# flute.net
KiCad netlist of a schematic drawn in EAGLE
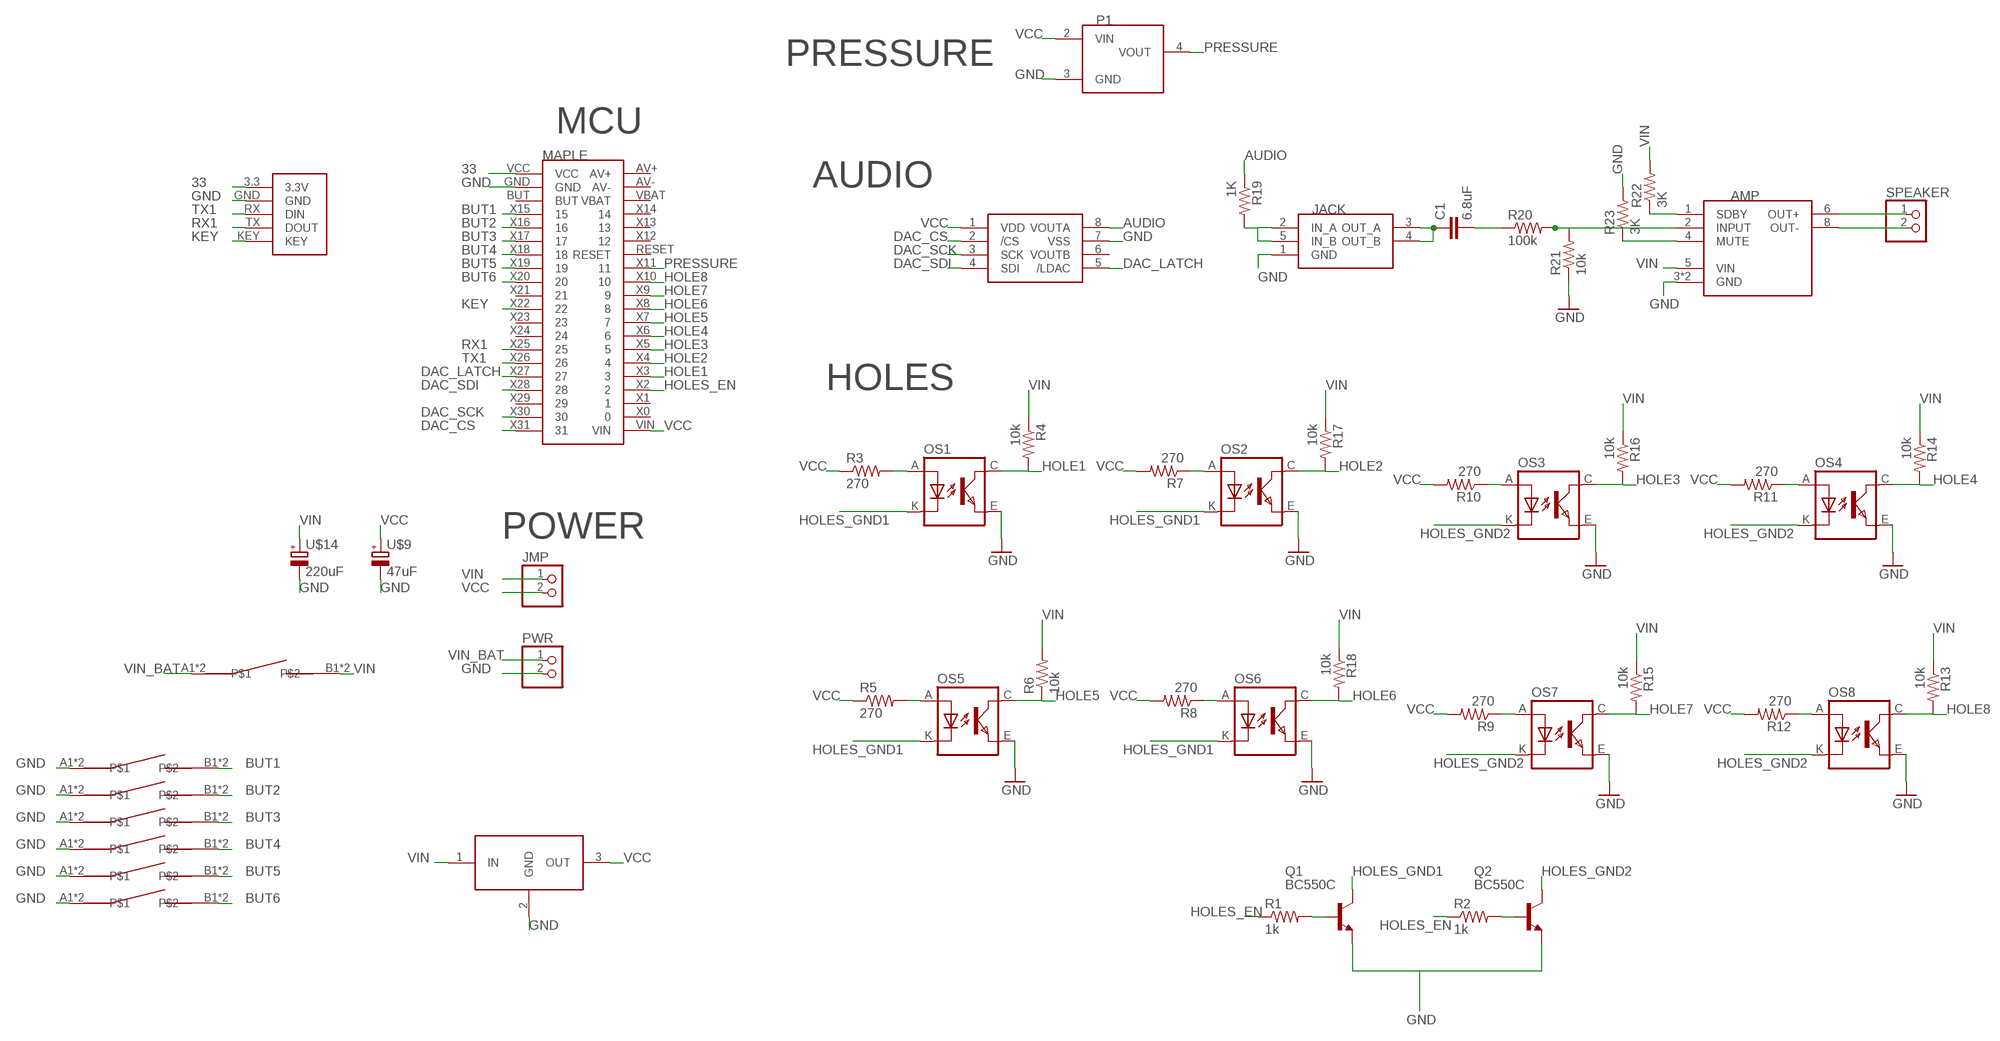
[diagram p0: schematic, sheet 1]

(export (version "E")
  (design (tool "Eeschema 10.0.6"))
  (components
    (comp (ref "AMP")
      (value "AN7511DIP8")
      (footprint "eagle-import:DIL08")
      (libsource (lib "eagle-import") (part "AN7511DIP8"))
    )
    (comp (ref "C1")
      (value "6.8uF")
      (footprint "eagle-import:0805")
      (libsource (lib "eagle-import") (part "CAP0805"))
    )
    (comp (ref "JACK")
      (value "JACK")
      (footprint "eagle-import:3F07")
      (libsource (lib "eagle-import") (part "JACK"))
    )
    (comp (ref "JMP")
      (value "CONNEC_1X02BASIC")
      (footprint "eagle-import:CONNEC_1X02")
      (libsource (lib "eagle-import") (part "CONNEC_1X02BASIC"))
    )
    (comp (ref "MAPLE")
      (value "MAPLE_MINI")
      (footprint "eagle-import:CONNEC_2X20")
      (libsource (lib "eagle-import") (part "MAPLE_MINI"))
    )
    (comp (ref "OS1")
      (value "TCRT5000")
      (footprint "eagle-import:TCRT5000")
      (libsource (lib "eagle-import") (part "TCRT5000"))
    )
    (comp (ref "OS2")
      (value "TCRT5000")
      (footprint "eagle-import:TCRT5000")
      (libsource (lib "eagle-import") (part "TCRT5000"))
    )
    (comp (ref "OS3")
      (value "TCRT5000")
      (footprint "eagle-import:TCRT5000")
      (libsource (lib "eagle-import") (part "TCRT5000"))
    )
    (comp (ref "OS4")
      (value "TCRT5000")
      (footprint "eagle-import:TCRT5000")
      (libsource (lib "eagle-import") (part "TCRT5000"))
    )
    (comp (ref "OS5")
      (value "TCRT5000")
      (footprint "eagle-import:TCRT5000")
      (libsource (lib "eagle-import") (part "TCRT5000"))
    )
    (comp (ref "OS6")
      (value "TCRT5000")
      (footprint "eagle-import:TCRT5000")
      (libsource (lib "eagle-import") (part "TCRT5000"))
    )
    (comp (ref "OS7")
      (value "TCRT5000")
      (footprint "eagle-import:TCRT5000")
      (libsource (lib "eagle-import") (part "TCRT5000"))
    )
    (comp (ref "OS8")
      (value "TCRT5000")
      (footprint "eagle-import:TCRT5000")
      (libsource (lib "eagle-import") (part "TCRT5000"))
    )
    (comp (ref "P1")
      (value "PRESSURE_SENSOR")
      (footprint "eagle-import:MPXV5050GP")
      (libsource (lib "eagle-import") (part "PRESSURE_SENSOR"))
    )
    (comp (ref "PWR")
      (value "CONNEC_1X02BASIC")
      (footprint "eagle-import:CONNEC_1X02")
      (libsource (lib "eagle-import") (part "CONNEC_1X02BASIC"))
    )
    (comp (ref "Q1")
      (value "BC550C")
      (footprint "eagle-import:TO92-EBC")
      (libsource (lib "eagle-import") (part "BC550C"))
    )
    (comp (ref "Q2")
      (value "BC550C")
      (footprint "eagle-import:TO92-EBC")
      (libsource (lib "eagle-import") (part "BC550C"))
    )
    (comp (ref "R1")
      (value "1k")
      (footprint "eagle-import:0805")
      (libsource (lib "eagle-import") (part "RESISTOR0805-RES"))
    )
    (comp (ref "R2")
      (value "1k")
      (footprint "eagle-import:0805")
      (libsource (lib "eagle-import") (part "RESISTOR0805-RES"))
    )
    (comp (ref "R3")
      (value "270")
      (footprint "eagle-import:0805")
      (libsource (lib "eagle-import") (part "RESISTOR0805-RES"))
    )
    (comp (ref "R4")
      (value "10k")
      (footprint "eagle-import:0805")
      (libsource (lib "eagle-import") (part "RESISTOR0805-RES"))
    )
    (comp (ref "R5")
      (value "270")
      (footprint "eagle-import:0805")
      (libsource (lib "eagle-import") (part "RESISTOR0805-RES"))
    )
    (comp (ref "R6")
      (value "10k")
      (footprint "eagle-import:0805")
      (libsource (lib "eagle-import") (part "RESISTOR0805-RES"))
    )
    (comp (ref "R7")
      (value "270")
      (footprint "eagle-import:0805")
      (libsource (lib "eagle-import") (part "RESISTOR0805-RES"))
    )
    (comp (ref "R8")
      (value "270")
      (footprint "eagle-import:0805")
      (libsource (lib "eagle-import") (part "RESISTOR0805-RES"))
    )
    (comp (ref "R9")
      (value "270")
      (footprint "eagle-import:0805")
      (libsource (lib "eagle-import") (part "RESISTOR0805-RES"))
    )
    (comp (ref "R10")
      (value "270")
      (footprint "eagle-import:0805")
      (libsource (lib "eagle-import") (part "RESISTOR0805-RES"))
    )
    (comp (ref "R11")
      (value "270")
      (footprint "eagle-import:0805")
      (libsource (lib "eagle-import") (part "RESISTOR0805-RES"))
    )
    (comp (ref "R12")
      (value "270")
      (footprint "eagle-import:0805")
      (libsource (lib "eagle-import") (part "RESISTOR0805-RES"))
    )
    (comp (ref "R13")
      (value "10k")
      (footprint "eagle-import:0805")
      (libsource (lib "eagle-import") (part "RESISTOR0805-RES"))
    )
    (comp (ref "R14")
      (value "10k")
      (footprint "eagle-import:0805")
      (libsource (lib "eagle-import") (part "RESISTOR0805-RES"))
    )
    (comp (ref "R15")
      (value "10k")
      (footprint "eagle-import:0805")
      (libsource (lib "eagle-import") (part "RESISTOR0805-RES"))
    )
    (comp (ref "R16")
      (value "10k")
      (footprint "eagle-import:0805")
      (libsource (lib "eagle-import") (part "RESISTOR0805-RES"))
    )
    (comp (ref "R17")
      (value "10k")
      (footprint "eagle-import:0805")
      (libsource (lib "eagle-import") (part "RESISTOR0805-RES"))
    )
    (comp (ref "R18")
      (value "10k")
      (footprint "eagle-import:0805")
      (libsource (lib "eagle-import") (part "RESISTOR0805-RES"))
    )
    (comp (ref "R19")
      (value "1K")
      (footprint "eagle-import:0805")
      (libsource (lib "eagle-import") (part "RESISTOR0805-RES"))
    )
    (comp (ref "R20")
      (value "100k")
      (footprint "eagle-import:0805")
      (libsource (lib "eagle-import") (part "RESISTOR0805-RES"))
    )
    (comp (ref "R21")
      (value "10k")
      (footprint "eagle-import:0805")
      (libsource (lib "eagle-import") (part "RESISTOR0805-RES"))
    )
    (comp (ref "R22")
      (value "3K")
      (footprint "eagle-import:0805")
      (libsource (lib "eagle-import") (part "RESISTOR0805-RES"))
    )
    (comp (ref "R23")
      (value "3K")
      (footprint "eagle-import:0805")
      (libsource (lib "eagle-import") (part "RESISTOR0805-RES"))
    )
    (comp (ref "SPEAKER")
      (value "CONNEC_1X02BASIC")
      (footprint "eagle-import:CONNEC_1X02")
      (libsource (lib "eagle-import") (part "CONNEC_1X02BASIC"))
    )
    (comp (ref "U$9")
      (value "47uF")
      (footprint "eagle-import:PANASONIC_D")
      (libsource (lib "eagle-import") (part "CPOL_EUPANASONIC_D"))
    )
    (comp (ref "U$14")
      (value "220uF")
      (footprint "eagle-import:PANASONIC_D8")
      (libsource (lib "eagle-import") (part "CPOL_EUPANASONIC_D8"))
    )
    (comp (ref "U$16")
      (value "SWITCHKCD11")
      (footprint "eagle-import:KCD11")
      (libsource (lib "eagle-import") (part "SWITCHKCD11"))
    )
    (comp (ref "U$17")
      (value "MCP4822")
      (footprint "eagle-import:DIL08")
      (libsource (lib "eagle-import") (part "RHOBAN_MCP4822"))
    )
    (comp (ref "U$18")
      (value "SWITCH6X6X10")
      (footprint "eagle-import:SWITCH_6X6X10")
      (libsource (lib "eagle-import") (part "SWITCH6X6X10"))
    )
    (comp (ref "U$19")
      (value "SWITCH6X6X10")
      (footprint "eagle-import:SWITCH_6X6X10")
      (libsource (lib "eagle-import") (part "SWITCH6X6X10"))
    )
    (comp (ref "U$20")
      (value "SWITCH6X6X10")
      (footprint "eagle-import:SWITCH_6X6X10")
      (libsource (lib "eagle-import") (part "SWITCH6X6X10"))
    )
    (comp (ref "U$21")
      (value "SWITCH6X6X10")
      (footprint "eagle-import:SWITCH_6X6X10")
      (libsource (lib "eagle-import") (part "SWITCH6X6X10"))
    )
    (comp (ref "U$22")
      (value "SWITCH6X6X10")
      (footprint "eagle-import:SWITCH_6X6X10")
      (libsource (lib "eagle-import") (part "SWITCH6X6X10"))
    )
    (comp (ref "U$23")
      (value "SWITCH6X6X10")
      (footprint "eagle-import:SWITCH_6X6X10")
      (libsource (lib "eagle-import") (part "SWITCH6X6X10"))
    )
    (comp (ref "U$24")
      (value "HC05")
      (footprint "eagle-import:HC-05")
      (libsource (lib "eagle-import") (part "HC05"))
    )
    (comp (ref "U$25")
      (value "MCP1703T-5002EDB")
      (footprint "eagle-import:SOT223")
      (libsource (lib "eagle-import") (part "MCP1703T-5002EDB"))
    )
  )
  (nets
    (net (code "1") (name "/33") (class "Default")
      (node (ref "MAPLE") (pin "VCC") (pinfunction "VCC_VCC") (pintype "bidirectional"))
      (node (ref "U$24") (pin "3.3") (pinfunction "3.3V_3.3") (pintype "bidirectional"))
    )
    (net (code "2") (name "/AUDIO") (class "Default")
      (node (ref "R19") (pin "1") (pinfunction "1_1") (pintype "passive"))
      (node (ref "U$17") (pin "8") (pinfunction "VOUTA_8") (pintype "bidirectional"))
    )
    (net (code "3") (name "/BUT1") (class "Default")
      (node (ref "MAPLE") (pin "X15") (pinfunction "15_X15") (pintype "bidirectional"))
      (node (ref "U$18") (pin "B1") (pinfunction "P$2_B1") (pintype "bidirectional"))
      (node (ref "U$18") (pin "B2") (pinfunction "P$2_B2") (pintype "bidirectional"))
    )
    (net (code "4") (name "/BUT2") (class "Default")
      (node (ref "MAPLE") (pin "X16") (pinfunction "16_X16") (pintype "bidirectional"))
      (node (ref "U$19") (pin "B1") (pinfunction "P$2_B1") (pintype "bidirectional"))
      (node (ref "U$19") (pin "B2") (pinfunction "P$2_B2") (pintype "bidirectional"))
    )
    (net (code "5") (name "/BUT3") (class "Default")
      (node (ref "MAPLE") (pin "X17") (pinfunction "17_X17") (pintype "bidirectional"))
      (node (ref "U$20") (pin "B1") (pinfunction "P$2_B1") (pintype "bidirectional"))
      (node (ref "U$20") (pin "B2") (pinfunction "P$2_B2") (pintype "bidirectional"))
    )
    (net (code "6") (name "/BUT4") (class "Default")
      (node (ref "MAPLE") (pin "X18") (pinfunction "18_X18") (pintype "bidirectional"))
      (node (ref "U$21") (pin "B1") (pinfunction "P$2_B1") (pintype "bidirectional"))
      (node (ref "U$21") (pin "B2") (pinfunction "P$2_B2") (pintype "bidirectional"))
    )
    (net (code "7") (name "/BUT5") (class "Default")
      (node (ref "MAPLE") (pin "X19") (pinfunction "19_X19") (pintype "bidirectional"))
      (node (ref "U$22") (pin "B1") (pinfunction "P$2_B1") (pintype "bidirectional"))
      (node (ref "U$22") (pin "B2") (pinfunction "P$2_B2") (pintype "bidirectional"))
    )
    (net (code "8") (name "/BUT6") (class "Default")
      (node (ref "MAPLE") (pin "X20") (pinfunction "20_X20") (pintype "bidirectional"))
      (node (ref "U$23") (pin "B1") (pinfunction "P$2_B1") (pintype "bidirectional"))
      (node (ref "U$23") (pin "B2") (pinfunction "P$2_B2") (pintype "bidirectional"))
    )
    (net (code "9") (name "/DAC_CS") (class "Default")
      (node (ref "MAPLE") (pin "X31") (pinfunction "31_X31") (pintype "bidirectional"))
      (node (ref "U$17") (pin "2") (pinfunction "/CS_2") (pintype "bidirectional"))
    )
    (net (code "10") (name "/DAC_LATCH") (class "Default")
      (node (ref "MAPLE") (pin "X27") (pinfunction "27_X27") (pintype "bidirectional"))
      (node (ref "U$17") (pin "5") (pinfunction "/LDAC_5") (pintype "bidirectional"))
    )
    (net (code "11") (name "/DAC_SCK") (class "Default")
      (node (ref "MAPLE") (pin "X30") (pinfunction "30_X30") (pintype "bidirectional"))
      (node (ref "U$17") (pin "3") (pinfunction "SCK_3") (pintype "bidirectional"))
    )
    (net (code "12") (name "/DAC_SDI") (class "Default")
      (node (ref "MAPLE") (pin "X28") (pinfunction "28_X28") (pintype "bidirectional"))
      (node (ref "U$17") (pin "4") (pinfunction "SDI_4") (pintype "bidirectional"))
    )
    (net (code "13") (name "/HOLE1") (class "Default")
      (node (ref "MAPLE") (pin "X3") (pinfunction "3_X3") (pintype "bidirectional"))
      (node (ref "OS1") (pin "C") (pinfunction "COLLECTOR_C") (pintype "passive"))
      (node (ref "R4") (pin "2") (pinfunction "2_2") (pintype "passive"))
    )
    (net (code "14") (name "/HOLE2") (class "Default")
      (node (ref "MAPLE") (pin "X4") (pinfunction "4_X4") (pintype "bidirectional"))
      (node (ref "OS2") (pin "C") (pinfunction "COLLECTOR_C") (pintype "passive"))
      (node (ref "R17") (pin "2") (pinfunction "2_2") (pintype "passive"))
    )
    (net (code "15") (name "/HOLE3") (class "Default")
      (node (ref "MAPLE") (pin "X5") (pinfunction "5_X5") (pintype "bidirectional"))
      (node (ref "OS3") (pin "C") (pinfunction "COLLECTOR_C") (pintype "passive"))
      (node (ref "R16") (pin "2") (pinfunction "2_2") (pintype "passive"))
    )
    (net (code "16") (name "/HOLE4") (class "Default")
      (node (ref "MAPLE") (pin "X6") (pinfunction "6_X6") (pintype "bidirectional"))
      (node (ref "OS4") (pin "C") (pinfunction "COLLECTOR_C") (pintype "passive"))
      (node (ref "R14") (pin "2") (pinfunction "2_2") (pintype "passive"))
    )
    (net (code "17") (name "/HOLE5") (class "Default")
      (node (ref "MAPLE") (pin "X7") (pinfunction "7_X7") (pintype "bidirectional"))
      (node (ref "OS5") (pin "C") (pinfunction "COLLECTOR_C") (pintype "passive"))
      (node (ref "R6") (pin "1") (pinfunction "1_1") (pintype "passive"))
    )
    (net (code "18") (name "/HOLE6") (class "Default")
      (node (ref "MAPLE") (pin "X8") (pinfunction "8_X8") (pintype "bidirectional"))
      (node (ref "OS6") (pin "C") (pinfunction "COLLECTOR_C") (pintype "passive"))
      (node (ref "R18") (pin "2") (pinfunction "2_2") (pintype "passive"))
    )
    (net (code "19") (name "/HOLE7") (class "Default")
      (node (ref "MAPLE") (pin "X9") (pinfunction "9_X9") (pintype "bidirectional"))
      (node (ref "OS7") (pin "C") (pinfunction "COLLECTOR_C") (pintype "passive"))
      (node (ref "R15") (pin "2") (pinfunction "2_2") (pintype "passive"))
    )
    (net (code "20") (name "/HOLE8") (class "Default")
      (node (ref "MAPLE") (pin "X10") (pinfunction "10_X10") (pintype "bidirectional"))
      (node (ref "OS8") (pin "C") (pinfunction "COLLECTOR_C") (pintype "passive"))
      (node (ref "R13") (pin "2") (pinfunction "2_2") (pintype "passive"))
    )
    (net (code "21") (name "/HOLES_EN") (class "Default")
      (node (ref "MAPLE") (pin "X2") (pinfunction "2_X2") (pintype "bidirectional"))
      (node (ref "R1") (pin "1") (pinfunction "1_1") (pintype "passive"))
      (node (ref "R2") (pin "1") (pinfunction "1_1") (pintype "passive"))
    )
    (net (code "22") (name "/HOLES_GND1") (class "Default")
      (node (ref "OS1") (pin "K") (pinfunction "CATHODE_K") (pintype "passive"))
      (node (ref "OS2") (pin "K") (pinfunction "CATHODE_K") (pintype "passive"))
      (node (ref "OS5") (pin "K") (pinfunction "CATHODE_K") (pintype "passive"))
      (node (ref "OS6") (pin "K") (pinfunction "CATHODE_K") (pintype "passive"))
      (node (ref "Q1") (pin "C") (pinfunction "C_C") (pintype "passive"))
    )
    (net (code "23") (name "/HOLES_GND2") (class "Default")
      (node (ref "OS3") (pin "K") (pinfunction "CATHODE_K") (pintype "passive"))
      (node (ref "OS4") (pin "K") (pinfunction "CATHODE_K") (pintype "passive"))
      (node (ref "OS7") (pin "K") (pinfunction "CATHODE_K") (pintype "passive"))
      (node (ref "OS8") (pin "K") (pinfunction "CATHODE_K") (pintype "passive"))
      (node (ref "Q2") (pin "C") (pinfunction "C_C") (pintype "passive"))
    )
    (net (code "24") (name "/KEY") (class "Default")
      (node (ref "MAPLE") (pin "X22") (pinfunction "22_X22") (pintype "bidirectional"))
      (node (ref "U$24") (pin "KEY") (pinfunction "KEY_KEY") (pintype "bidirectional"))
    )
    (net (code "25") (name "/PRESSURE") (class "Default")
      (node (ref "MAPLE") (pin "X11") (pinfunction "11_X11") (pintype "bidirectional"))
      (node (ref "P1") (pin "4") (pinfunction "VOUT_4") (pintype "bidirectional"))
    )
    (net (code "26") (name "/RX1") (class "Default")
      (node (ref "MAPLE") (pin "X25") (pinfunction "25_X25") (pintype "bidirectional"))
      (node (ref "U$24") (pin "TX") (pinfunction "DOUT_TX") (pintype "bidirectional"))
    )
    (net (code "27") (name "/TX1") (class "Default")
      (node (ref "MAPLE") (pin "X26") (pinfunction "26_X26") (pintype "bidirectional"))
      (node (ref "U$24") (pin "RX") (pinfunction "DIN_RX") (pintype "bidirectional"))
    )
    (net (code "28") (name "/VCC") (class "Default")
      (node (ref "JMP") (pin "2") (pinfunction "2_2") (pintype "passive"))
      (node (ref "MAPLE") (pin "VIN") (pinfunction "VIN_VIN") (pintype "bidirectional"))
      (node (ref "P1") (pin "2") (pinfunction "VIN_2") (pintype "bidirectional"))
      (node (ref "R10") (pin "2") (pinfunction "2_2") (pintype "passive"))
      (node (ref "R11") (pin "2") (pinfunction "2_2") (pintype "passive"))
      (node (ref "R12") (pin "2") (pinfunction "2_2") (pintype "passive"))
      (node (ref "R3") (pin "1") (pinfunction "1_1") (pintype "passive"))
      (node (ref "R5") (pin "1") (pinfunction "1_1") (pintype "passive"))
      (node (ref "R7") (pin "2") (pinfunction "2_2") (pintype "passive"))
      (node (ref "R8") (pin "2") (pinfunction "2_2") (pintype "passive"))
      (node (ref "R9") (pin "2") (pinfunction "2_2") (pintype "passive"))
      (node (ref "U$17") (pin "1") (pinfunction "VDD_1") (pintype "bidirectional"))
      (node (ref "U$25") (pin "3") (pinfunction "OUT_3") (pintype "bidirectional"))
      (node (ref "U$9") (pin "+") (pinfunction "+_+") (pintype "passive"))
    )
    (net (code "29") (name "/VIN") (class "Default")
      (node (ref "AMP") (pin "5") (pinfunction "VIN_5") (pintype "bidirectional"))
      (node (ref "JMP") (pin "1") (pinfunction "1_1") (pintype "passive"))
      (node (ref "R13") (pin "1") (pinfunction "1_1") (pintype "passive"))
      (node (ref "R14") (pin "1") (pinfunction "1_1") (pintype "passive"))
      (node (ref "R15") (pin "1") (pinfunction "1_1") (pintype "passive"))
      (node (ref "R16") (pin "1") (pinfunction "1_1") (pintype "passive"))
      (node (ref "R17") (pin "1") (pinfunction "1_1") (pintype "passive"))
      (node (ref "R18") (pin "1") (pinfunction "1_1") (pintype "passive"))
      (node (ref "R22") (pin "2") (pinfunction "2_2") (pintype "passive"))
      (node (ref "R4") (pin "1") (pinfunction "1_1") (pintype "passive"))
      (node (ref "R6") (pin "2") (pinfunction "2_2") (pintype "passive"))
      (node (ref "U$14") (pin "+") (pinfunction "+_+") (pintype "passive"))
      (node (ref "U$16") (pin "B1") (pinfunction "P$2_B1") (pintype "bidirectional"))
      (node (ref "U$16") (pin "B2") (pinfunction "P$2_B2") (pintype "bidirectional"))
      (node (ref "U$25") (pin "1") (pinfunction "IN_1") (pintype "bidirectional"))
    )
    (net (code "30") (name "/VIN_BAT") (class "Default")
      (node (ref "PWR") (pin "1") (pinfunction "1_1") (pintype "passive"))
      (node (ref "U$16") (pin "A1") (pinfunction "P$1_A1") (pintype "bidirectional"))
      (node (ref "U$16") (pin "A2") (pinfunction "P$1_A2") (pintype "bidirectional"))
    )
    (net (code "31") (name "GND") (class "Default")
      (node (ref "AMP") (pin "3") (pinfunction "GND_3") (pintype "bidirectional"))
      (node (ref "AMP") (pin "7") (pinfunction "GND_7") (pintype "bidirectional"))
      (node (ref "JACK") (pin "1") (pinfunction "GND_1") (pintype "bidirectional"))
      (node (ref "MAPLE") (pin "GND") (pinfunction "GND_GND") (pintype "bidirectional"))
      (node (ref "OS1") (pin "E") (pinfunction "EMITTER_E") (pintype "passive"))
      (node (ref "OS2") (pin "E") (pinfunction "EMITTER_E") (pintype "passive"))
      (node (ref "OS3") (pin "E") (pinfunction "EMITTER_E") (pintype "passive"))
      (node (ref "OS4") (pin "E") (pinfunction "EMITTER_E") (pintype "passive"))
      (node (ref "OS5") (pin "E") (pinfunction "EMITTER_E") (pintype "passive"))
      (node (ref "OS6") (pin "E") (pinfunction "EMITTER_E") (pintype "passive"))
      (node (ref "OS7") (pin "E") (pinfunction "EMITTER_E") (pintype "passive"))
      (node (ref "OS8") (pin "E") (pinfunction "EMITTER_E") (pintype "passive"))
      (node (ref "P1") (pin "3") (pinfunction "GND_3") (pintype "bidirectional"))
      (node (ref "PWR") (pin "2") (pinfunction "2_2") (pintype "passive"))
      (node (ref "Q1") (pin "E") (pinfunction "E_E") (pintype "passive"))
      (node (ref "Q2") (pin "E") (pinfunction "E_E") (pintype "passive"))
      (node (ref "R21") (pin "1") (pinfunction "1_1") (pintype "passive"))
      (node (ref "R23") (pin "2") (pinfunction "2_2") (pintype "passive"))
      (node (ref "U$14") (pin "-") (pinfunction "-_-") (pintype "passive"))
      (node (ref "U$17") (pin "7") (pinfunction "VSS_7") (pintype "bidirectional"))
      (node (ref "U$18") (pin "A1") (pinfunction "P$1_A1") (pintype "bidirectional"))
      (node (ref "U$18") (pin "A2") (pinfunction "P$1_A2") (pintype "bidirectional"))
      (node (ref "U$19") (pin "A1") (pinfunction "P$1_A1") (pintype "bidirectional"))
      (node (ref "U$19") (pin "A2") (pinfunction "P$1_A2") (pintype "bidirectional"))
      (node (ref "U$20") (pin "A1") (pinfunction "P$1_A1") (pintype "bidirectional"))
      (node (ref "U$20") (pin "A2") (pinfunction "P$1_A2") (pintype "bidirectional"))
      (node (ref "U$21") (pin "A1") (pinfunction "P$1_A1") (pintype "bidirectional"))
      (node (ref "U$21") (pin "A2") (pinfunction "P$1_A2") (pintype "bidirectional"))
      (node (ref "U$22") (pin "A1") (pinfunction "P$1_A1") (pintype "bidirectional"))
      (node (ref "U$22") (pin "A2") (pinfunction "P$1_A2") (pintype "bidirectional"))
      (node (ref "U$23") (pin "A1") (pinfunction "P$1_A1") (pintype "bidirectional"))
      (node (ref "U$23") (pin "A2") (pinfunction "P$1_A2") (pintype "bidirectional"))
      (node (ref "U$24") (pin "GND") (pinfunction "GND_GND") (pintype "bidirectional"))
      (node (ref "U$25") (pin "2") (pinfunction "GND_2") (pintype "bidirectional"))
      (node (ref "U$9") (pin "-") (pinfunction "-_-") (pintype "passive"))
    )
    (net (code "32") (name "Net-(AMP-INPUT)") (class "Default")
      (node (ref "AMP") (pin "2") (pinfunction "INPUT_2") (pintype "bidirectional"))
      (node (ref "R20") (pin "2") (pinfunction "2_2") (pintype "passive"))
      (node (ref "R21") (pin "2") (pinfunction "2_2") (pintype "passive"))
    )
    (net (code "33") (name "Net-(AMP-MUTE)") (class "Default")
      (node (ref "AMP") (pin "4") (pinfunction "MUTE_4") (pintype "bidirectional"))
      (node (ref "R23") (pin "1") (pinfunction "1_1") (pintype "passive"))
    )
    (net (code "34") (name "Net-(AMP-OUT+)") (class "Default")
      (node (ref "AMP") (pin "6") (pinfunction "OUT+_6") (pintype "bidirectional"))
      (node (ref "SPEAKER") (pin "1") (pinfunction "1_1") (pintype "passive"))
    )
    (net (code "35") (name "Net-(AMP-OUT-)") (class "Default")
      (node (ref "AMP") (pin "8") (pinfunction "OUT-_8") (pintype "bidirectional"))
      (node (ref "SPEAKER") (pin "2") (pinfunction "2_2") (pintype "passive"))
    )
    (net (code "36") (name "Net-(AMP-SDBY)") (class "Default")
      (node (ref "AMP") (pin "1") (pinfunction "SDBY_1") (pintype "bidirectional"))
      (node (ref "R22") (pin "1") (pinfunction "1_1") (pintype "passive"))
    )
    (net (code "37") (name "Net-(C1-Pad2)") (class "Default")
      (node (ref "C1") (pin "2") (pinfunction "2_2") (pintype "passive"))
      (node (ref "R20") (pin "1") (pinfunction "1_1") (pintype "passive"))
    )
    (net (code "38") (name "Net-(JACK-IN_A)") (class "Default")
      (node (ref "JACK") (pin "2") (pinfunction "IN_A_2") (pintype "bidirectional"))
      (node (ref "JACK") (pin "5") (pinfunction "IN_B_5") (pintype "bidirectional"))
      (node (ref "R19") (pin "2") (pinfunction "2_2") (pintype "passive"))
    )
    (net (code "39") (name "Net-(JACK-OUT_A)") (class "Default")
      (node (ref "C1") (pin "1") (pinfunction "1_1") (pintype "passive"))
      (node (ref "JACK") (pin "3") (pinfunction "OUT_A_3") (pintype "bidirectional"))
      (node (ref "JACK") (pin "4") (pinfunction "OUT_B_4") (pintype "bidirectional"))
    )
    (net (code "40") (name "Net-(OS1-ANODE)") (class "Default")
      (node (ref "OS1") (pin "A") (pinfunction "ANODE_A") (pintype "passive"))
      (node (ref "R3") (pin "2") (pinfunction "2_2") (pintype "passive"))
    )
    (net (code "41") (name "Net-(OS2-ANODE)") (class "Default")
      (node (ref "OS2") (pin "A") (pinfunction "ANODE_A") (pintype "passive"))
      (node (ref "R7") (pin "1") (pinfunction "1_1") (pintype "passive"))
    )
    (net (code "42") (name "Net-(OS3-ANODE)") (class "Default")
      (node (ref "OS3") (pin "A") (pinfunction "ANODE_A") (pintype "passive"))
      (node (ref "R10") (pin "1") (pinfunction "1_1") (pintype "passive"))
    )
    (net (code "43") (name "Net-(OS4-ANODE)") (class "Default")
      (node (ref "OS4") (pin "A") (pinfunction "ANODE_A") (pintype "passive"))
      (node (ref "R11") (pin "1") (pinfunction "1_1") (pintype "passive"))
    )
    (net (code "44") (name "Net-(OS5-ANODE)") (class "Default")
      (node (ref "OS5") (pin "A") (pinfunction "ANODE_A") (pintype "passive"))
      (node (ref "R5") (pin "2") (pinfunction "2_2") (pintype "passive"))
    )
    (net (code "45") (name "Net-(OS6-ANODE)") (class "Default")
      (node (ref "OS6") (pin "A") (pinfunction "ANODE_A") (pintype "passive"))
      (node (ref "R8") (pin "1") (pinfunction "1_1") (pintype "passive"))
    )
    (net (code "46") (name "Net-(OS7-ANODE)") (class "Default")
      (node (ref "OS7") (pin "A") (pinfunction "ANODE_A") (pintype "passive"))
      (node (ref "R9") (pin "1") (pinfunction "1_1") (pintype "passive"))
    )
    (net (code "47") (name "Net-(OS8-ANODE)") (class "Default")
      (node (ref "OS8") (pin "A") (pinfunction "ANODE_A") (pintype "passive"))
      (node (ref "R12") (pin "1") (pinfunction "1_1") (pintype "passive"))
    )
    (net (code "48") (name "Net-(Q1-PadB)") (class "Default")
      (node (ref "Q1") (pin "B") (pinfunction "B_B") (pintype "passive"))
      (node (ref "R1") (pin "2") (pinfunction "2_2") (pintype "passive"))
    )
    (net (code "49") (name "Net-(Q2-PadB)") (class "Default")
      (node (ref "Q2") (pin "B") (pinfunction "B_B") (pintype "passive"))
      (node (ref "R2") (pin "2") (pinfunction "2_2") (pintype "passive"))
    )
    (net (code "50") (name "unconnected-(MAPLE-0-PadX0)") (class "Default")
      (node (ref "MAPLE") (pin "X0") (pinfunction "0_X0") (pintype "bidirectional"))
    )
    (net (code "51") (name "unconnected-(MAPLE-1-PadX1)") (class "Default")
      (node (ref "MAPLE") (pin "X1") (pinfunction "1_X1") (pintype "bidirectional"))
    )
    (net (code "52") (name "unconnected-(MAPLE-12-PadX12)") (class "Default")
      (node (ref "MAPLE") (pin "X12") (pinfunction "12_X12") (pintype "bidirectional"))
    )
    (net (code "53") (name "unconnected-(MAPLE-13-PadX13)") (class "Default")
      (node (ref "MAPLE") (pin "X13") (pinfunction "13_X13") (pintype "bidirectional"))
    )
    (net (code "54") (name "unconnected-(MAPLE-14-PadX14)") (class "Default")
      (node (ref "MAPLE") (pin "X14") (pinfunction "14_X14") (pintype "bidirectional"))
    )
    (net (code "55") (name "unconnected-(MAPLE-21-PadX21)") (class "Default")
      (node (ref "MAPLE") (pin "X21") (pinfunction "21_X21") (pintype "bidirectional"))
    )
    (net (code "56") (name "unconnected-(MAPLE-23-PadX23)") (class "Default")
      (node (ref "MAPLE") (pin "X23") (pinfunction "23_X23") (pintype "bidirectional"))
    )
    (net (code "57") (name "unconnected-(MAPLE-24-PadX24)") (class "Default")
      (node (ref "MAPLE") (pin "X24") (pinfunction "24_X24") (pintype "bidirectional"))
    )
    (net (code "58") (name "unconnected-(MAPLE-29-PadX29)") (class "Default")
      (node (ref "MAPLE") (pin "X29") (pinfunction "29_X29") (pintype "bidirectional"))
    )
    (net (code "59") (name "unconnected-(MAPLE-PadAV+)") (class "Default")
      (node (ref "MAPLE") (pin "AV+") (pinfunction "AV+_AV+") (pintype "bidirectional"))
    )
    (net (code "60") (name "unconnected-(MAPLE-PadAV-)") (class "Default")
      (node (ref "MAPLE") (pin "AV-") (pinfunction "AV-_AV-") (pintype "bidirectional"))
    )
    (net (code "61") (name "unconnected-(MAPLE-PadBUT)") (class "Default")
      (node (ref "MAPLE") (pin "BUT") (pinfunction "BUT_BUT") (pintype "bidirectional"))
    )
    (net (code "62") (name "unconnected-(MAPLE-PadRESET)") (class "Default")
      (node (ref "MAPLE") (pin "RESET") (pinfunction "RESET_RESET") (pintype "bidirectional"))
    )
    (net (code "63") (name "unconnected-(MAPLE-PadVBAT)") (class "Default")
      (node (ref "MAPLE") (pin "VBAT") (pinfunction "VBAT_VBAT") (pintype "bidirectional"))
    )
    (net (code "64") (name "unconnected-(U$17-VOUTB-Pad6)") (class "Default")
      (node (ref "U$17") (pin "6") (pinfunction "VOUTB_6") (pintype "bidirectional"))
    )
  )
)
